# Celsius-Temperature-Sensor.net
KiCad netlist of a schematic drawn in EAGLE
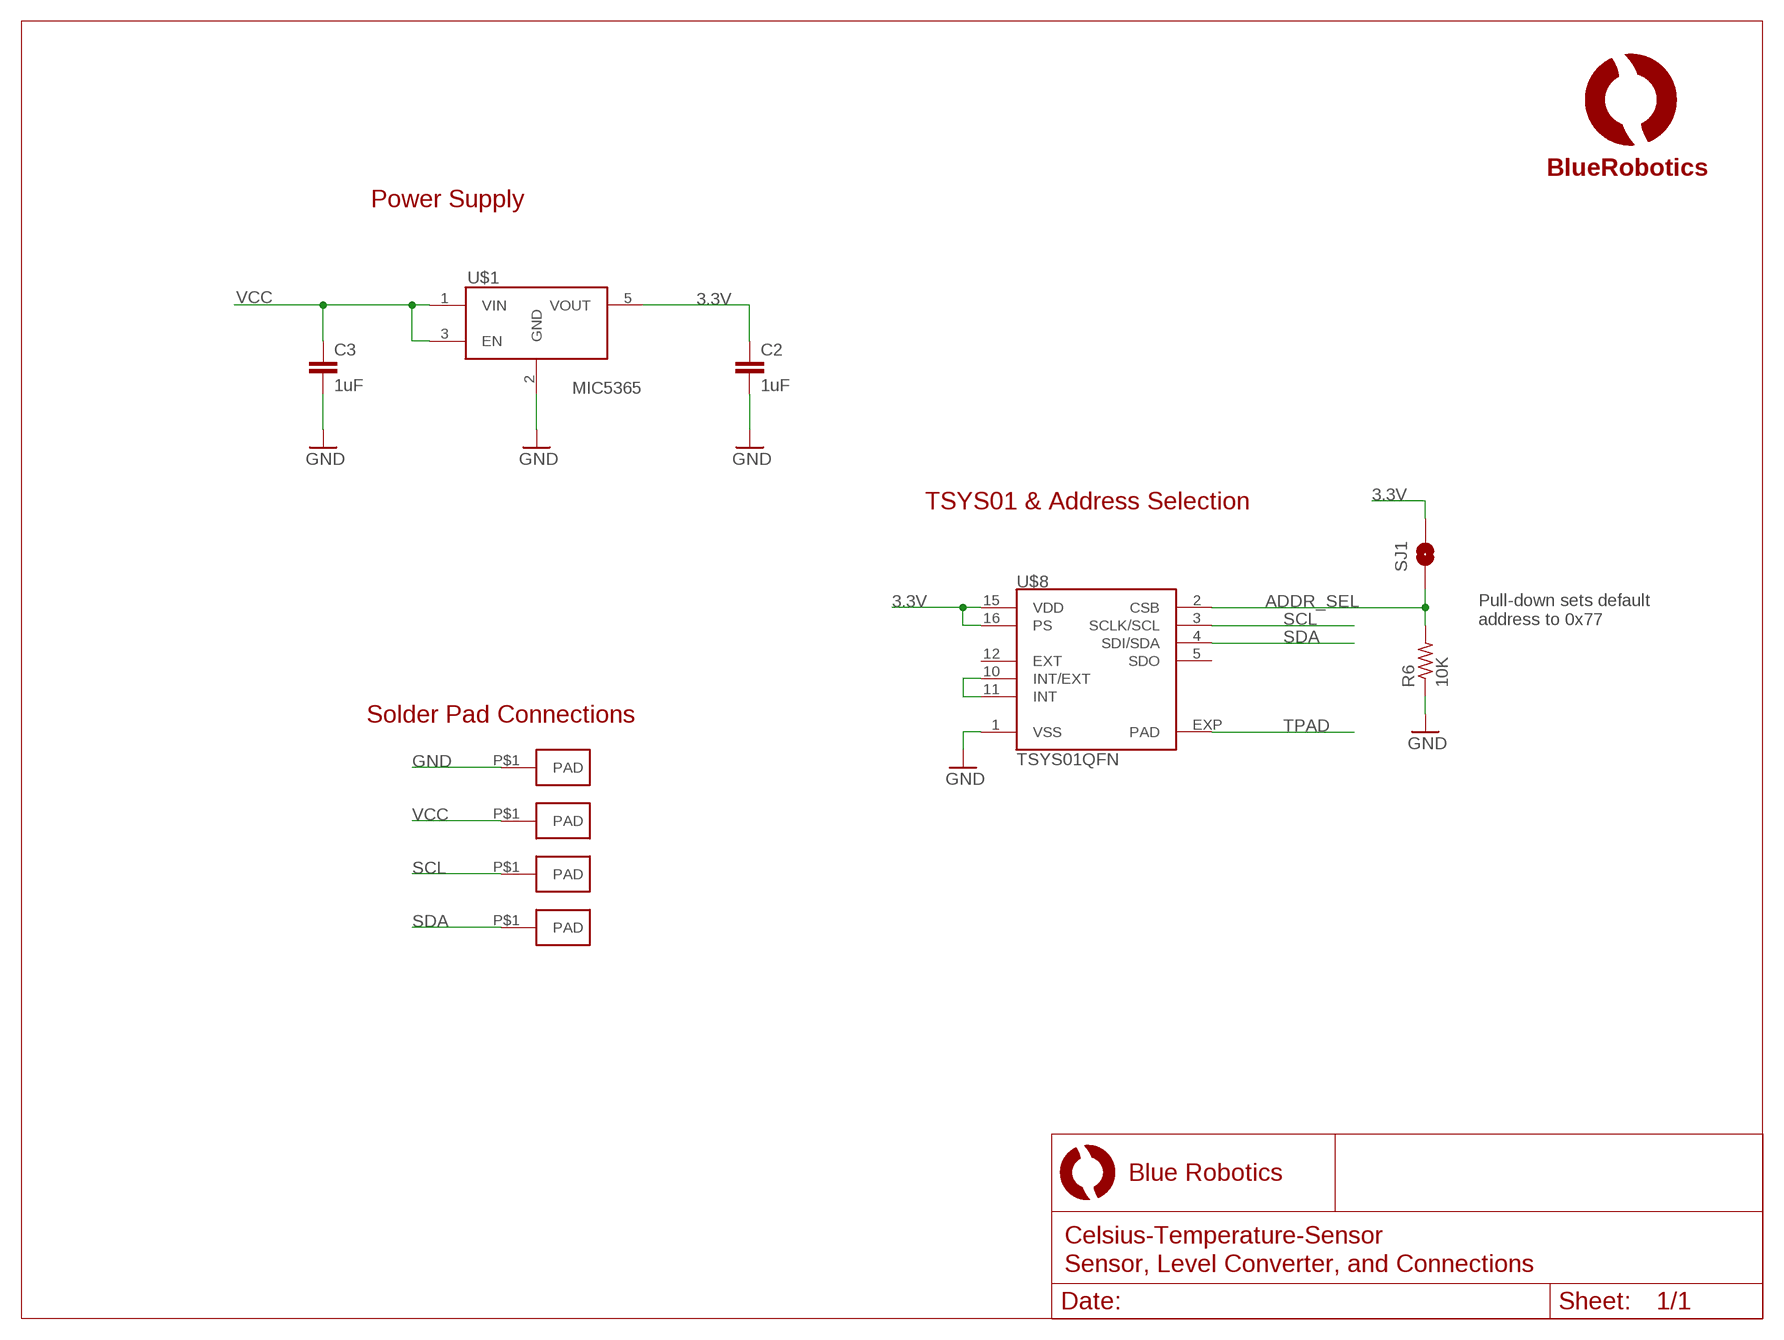
[diagram p0: schematic, sheet 1]

(export (version "E")
  (design (tool "Eeschema 10.0.6"))
  (components
    (comp (ref "C2")
      (value "1uF")
      (footprint "eagle-import:C0402")
      (libsource (lib "eagle-import") (part "C-EUC0402"))
    )
    (comp (ref "C3")
      (value "1uF")
      (footprint "eagle-import:C0402")
      (libsource (lib "eagle-import") (part "C-EUC0402"))
    )
    (comp (ref "R6")
      (value "10K")
      (footprint "eagle-import:R0402")
      (libsource (lib "eagle-import") (part "R-US_R0402"))
    )
    (comp (ref "SJ1")
      (value "JUMPER-PAD-2-NO")
      (footprint "eagle-import:PAD-JUMPER-2-NO_NO_SILK")
      (libsource (lib "eagle-import") (part "JUMPER-PAD-2-NO"))
    )
    (comp (ref "U$1")
      (value "VREG-MIC5365")
      (footprint "eagle-import:SC70-5L")
      (libsource (lib "eagle-import") (part "VREG-MIC5365"))
    )
    (comp (ref "U$3")
      (value "PAD1.5X3MM")
      (footprint "eagle-import:PAD-1.5X3MM")
      (libsource (lib "eagle-import") (part "PAD1.5X3MM"))
    )
    (comp (ref "U$4")
      (value "PAD1.5X3MM")
      (footprint "eagle-import:PAD-1.5X3MM")
      (libsource (lib "eagle-import") (part "PAD1.5X3MM"))
    )
    (comp (ref "U$5")
      (value "PAD1.5X3MM")
      (footprint "eagle-import:PAD-1.5X3MM")
      (libsource (lib "eagle-import") (part "PAD1.5X3MM"))
    )
    (comp (ref "U$6")
      (value "PAD1.5X3MM")
      (footprint "eagle-import:PAD-1.5X3MM")
      (libsource (lib "eagle-import") (part "PAD1.5X3MM"))
    )
    (comp (ref "U$7")
      (value "LOGOBR-LOGO-S")
      (footprint "eagle-import:BR-LOGO-SMALL")
      (libsource (lib "eagle-import") (part "LOGOBR-LOGO-S"))
    )
    (comp (ref "U$8")
      (value "TSYS01QFN")
      (footprint "eagle-import:QFN16-4X4")
      (libsource (lib "eagle-import") (part "TSYS01QFN"))
    )
  )
  (nets
    (net (code "1") (name "/3.3V") (class "Default")
      (node (ref "C2") (pin "1") (pinfunction "1_1") (pintype "passive"))
      (node (ref "SJ1") (pin "2") (pinfunction "2_2") (pintype "passive"))
      (node (ref "U$1") (pin "5") (pinfunction "VOUT_5") (pintype "bidirectional"))
      (node (ref "U$8") (pin "15") (pinfunction "VDD_15") (pintype "bidirectional"))
      (node (ref "U$8") (pin "16") (pinfunction "PS_16") (pintype "bidirectional"))
    )
    (net (code "2") (name "/ADDR_SEL") (class "Default")
      (node (ref "R6") (pin "2") (pinfunction "2_2") (pintype "passive"))
      (node (ref "SJ1") (pin "1") (pinfunction "1_1") (pintype "passive"))
      (node (ref "U$8") (pin "2") (pinfunction "CSB_2") (pintype "bidirectional"))
    )
    (net (code "3") (name "/SCL") (class "Default")
      (node (ref "U$5") (pin "P$1") (pinfunction "PAD_P$1") (pintype "bidirectional"))
      (node (ref "U$8") (pin "3") (pinfunction "SCLK/SCL_3") (pintype "bidirectional"))
    )
    (net (code "4") (name "/SDA") (class "Default")
      (node (ref "U$6") (pin "P$1") (pinfunction "PAD_P$1") (pintype "bidirectional"))
      (node (ref "U$8") (pin "4") (pinfunction "SDI/SDA_4") (pintype "bidirectional"))
    )
    (net (code "5") (name "/TPAD") (class "Default")
      (node (ref "U$8") (pin "EXP") (pinfunction "PAD_EXP") (pintype "bidirectional"))
    )
    (net (code "6") (name "/VCC") (class "Default")
      (node (ref "C3") (pin "1") (pinfunction "1_1") (pintype "passive"))
      (node (ref "U$1") (pin "1") (pinfunction "VIN_1") (pintype "bidirectional"))
      (node (ref "U$1") (pin "3") (pinfunction "EN_3") (pintype "bidirectional"))
      (node (ref "U$4") (pin "P$1") (pinfunction "PAD_P$1") (pintype "bidirectional"))
    )
    (net (code "7") (name "GND") (class "Default")
      (node (ref "C2") (pin "2") (pinfunction "2_2") (pintype "passive"))
      (node (ref "C3") (pin "2") (pinfunction "2_2") (pintype "passive"))
      (node (ref "R6") (pin "1") (pinfunction "1_1") (pintype "passive"))
      (node (ref "U$1") (pin "2") (pinfunction "GND_2") (pintype "bidirectional"))
      (node (ref "U$3") (pin "P$1") (pinfunction "PAD_P$1") (pintype "bidirectional"))
      (node (ref "U$8") (pin "1") (pinfunction "VSS_1") (pintype "bidirectional"))
    )
    (net (code "8") (name "Net-(U$8-INT)") (class "Default")
      (node (ref "U$8") (pin "10") (pinfunction "INT/EXT_10") (pintype "bidirectional"))
      (node (ref "U$8") (pin "11") (pinfunction "INT_11") (pintype "bidirectional"))
    )
    (net (code "9") (name "unconnected-(U$8-EXT-Pad12)") (class "Default")
      (node (ref "U$8") (pin "12") (pinfunction "EXT_12") (pintype "bidirectional"))
    )
    (net (code "10") (name "unconnected-(U$8-SDO-Pad5)") (class "Default")
      (node (ref "U$8") (pin "5") (pinfunction "SDO_5") (pintype "bidirectional"))
    )
  )
)
